# Inputs.net
KiCad netlist of a schematic drawn in Altium Designer
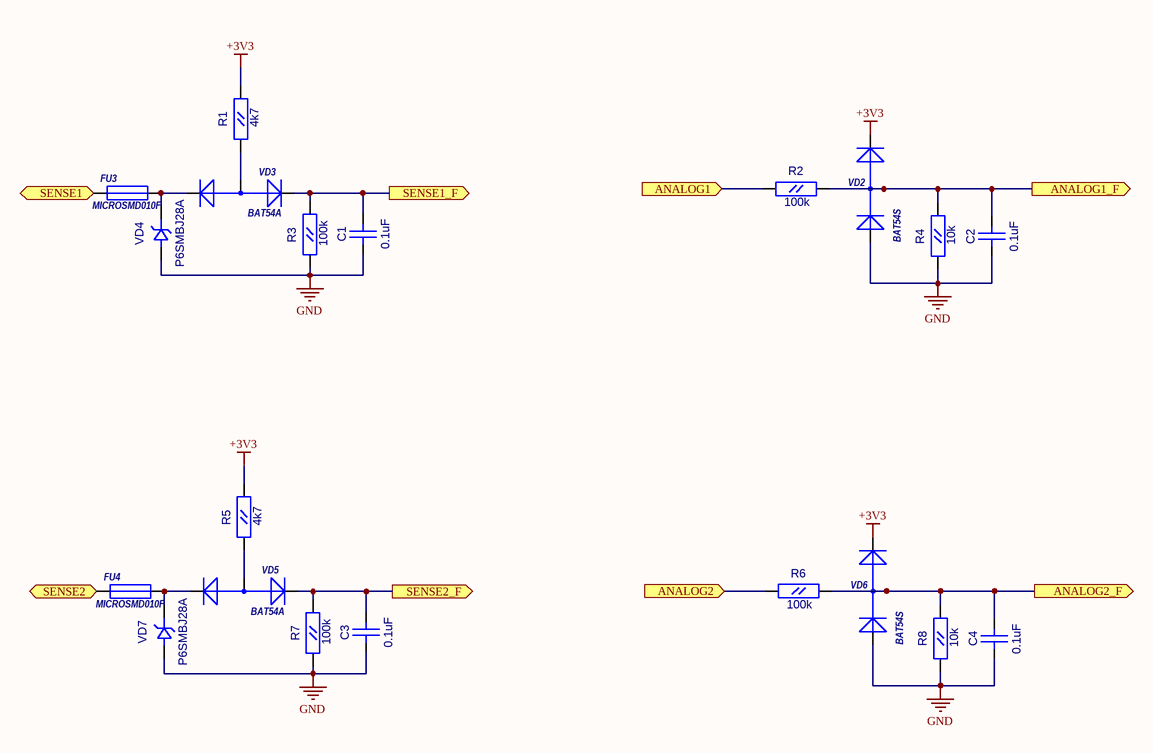
[diagram p0: Inputs.SchDoc]

(export (version "E")
  (design (tool "Eeschema 10.0.6"))
  (components
    (comp (ref "C1")
      (value "0.1uF")
      (footprint "CC0603")
      (description "CC0603")
      (libsource (lib "gprs_modem_2") (part "CC0603"))
    )
    (comp (ref "C2")
      (value "0.1uF")
      (footprint "CC0603")
      (description "CC0603")
      (libsource (lib "gprs_modem_2") (part "CC0603"))
    )
    (comp (ref "C3")
      (value "0.1uF")
      (footprint "CC0603")
      (description "CC0603")
      (libsource (lib "gprs_modem_2") (part "CC0603"))
    )
    (comp (ref "C4")
      (value "0.1uF")
      (footprint "CC0603")
      (description "CC0603")
      (libsource (lib "gprs_modem_2") (part "CC0603"))
    )
    (comp (ref "FU3")
      (value "MICROSMD010F")
      (footprint "RC1210")
      (description "MICROSMD")
      (libsource (lib "gprs_modem_2") (part "MICROSMD"))
    )
    (comp (ref "FU4")
      (value "MICROSMD010F")
      (footprint "RC1210")
      (description "MICROSMD")
      (libsource (lib "gprs_modem_2") (part "MICROSMD"))
    )
    (comp (ref "R1")
      (value "4k7")
      (footprint "RC0603")
      (description "RC0603")
      (libsource (lib "gprs_modem_2") (part "RC0603"))
    )
    (comp (ref "R2")
      (value "100k")
      (footprint "RC0603")
      (description "RC0603")
      (libsource (lib "gprs_modem_2") (part "RC0603"))
    )
    (comp (ref "R3")
      (value "100k")
      (footprint "RC0603")
      (description "RC0603")
      (libsource (lib "gprs_modem_2") (part "RC0603"))
    )
    (comp (ref "R4")
      (value "10k")
      (footprint "RC0603")
      (description "RC0603")
      (libsource (lib "gprs_modem_2") (part "RC0603"))
    )
    (comp (ref "R5")
      (value "4k7")
      (footprint "RC0603")
      (description "RC0603")
      (libsource (lib "gprs_modem_2") (part "RC0603"))
    )
    (comp (ref "R6")
      (value "100k")
      (footprint "RC0603")
      (description "RC0603")
      (libsource (lib "gprs_modem_2") (part "RC0603"))
    )
    (comp (ref "R7")
      (value "100k")
      (footprint "RC0603")
      (description "RC0603")
      (libsource (lib "gprs_modem_2") (part "RC0603"))
    )
    (comp (ref "R8")
      (value "10k")
      (footprint "RC0603")
      (description "RC0603")
      (libsource (lib "gprs_modem_2") (part "RC0603"))
    )
    (comp (ref "VD2")
      (value "BAT54S")
      (footprint "SOT-23(GSD)")
      (description "1.0 Ampere General Purpose Rectifier")
      (libsource (lib "gprs_modem_2") (part "BAT54S"))
    )
    (comp (ref "VD3")
      (value "BAT54A")
      (footprint "SOT-23(123)")
      (description "1.0 Ampere General Purpose Rectifier")
      (libsource (lib "gprs_modem_2") (part "BAT54A"))
    )
    (comp (ref "VD4")
      (value "P6SMBJ28A")
      (footprint "SMB")
      (description "SMBJ")
      (libsource (lib "gprs_modem_2") (part "SMBJ"))
    )
    (comp (ref "VD5")
      (value "BAT54A")
      (footprint "SOT-23(123)")
      (description "1.0 Ampere General Purpose Rectifier")
      (libsource (lib "gprs_modem_2") (part "BAT54A"))
    )
    (comp (ref "VD6")
      (value "BAT54S")
      (footprint "SOT-23(GSD)")
      (description "1.0 Ampere General Purpose Rectifier")
      (libsource (lib "gprs_modem_2") (part "BAT54S"))
    )
    (comp (ref "VD7")
      (value "P6SMBJ28A")
      (footprint "SMB")
      (description "SMBJ")
      (libsource (lib "gprs_modem_2") (part "SMBJ"))
    )
  )
  (nets
    (net (code "1") (name "+3V3") (class "Default")
      (node (ref "R1") (pin "2") (pinfunction "B_2") (pintype "passive"))
      (node (ref "R5") (pin "2") (pinfunction "B_2") (pintype "passive"))
      (node (ref "VD2") (pin "2") (pinfunction "K_2") (pintype "passive"))
      (node (ref "VD6") (pin "2") (pinfunction "K_2") (pintype "passive"))
    )
    (net (code "2") (name "/ANALOG1") (class "Default")
      (node (ref "R2") (pin "1") (pinfunction "A_1") (pintype "passive"))
    )
    (net (code "3") (name "/ANALOG1_F") (class "Default")
      (node (ref "C2") (pin "2") (pinfunction "B_2") (pintype "passive"))
      (node (ref "R2") (pin "2") (pinfunction "B_2") (pintype "passive"))
      (node (ref "R4") (pin "2") (pinfunction "B_2") (pintype "passive"))
      (node (ref "VD2") (pin "3") (pinfunction "AK_3") (pintype "passive"))
    )
    (net (code "4") (name "/ANALOG2") (class "Default")
      (node (ref "R6") (pin "1") (pinfunction "A_1") (pintype "passive"))
    )
    (net (code "5") (name "/ANALOG2_F") (class "Default")
      (node (ref "C4") (pin "2") (pinfunction "B_2") (pintype "passive"))
      (node (ref "R6") (pin "2") (pinfunction "B_2") (pintype "passive"))
      (node (ref "R8") (pin "2") (pinfunction "B_2") (pintype "passive"))
      (node (ref "VD6") (pin "3") (pinfunction "AK_3") (pintype "passive"))
    )
    (net (code "6") (name "/SENSE1") (class "Default") (node (ref "FU3") (pin "1") (pintype "passive")))
    (net (code "7") (name "/SENSE1_F") (class "Default")
      (node (ref "C1") (pin "2") (pinfunction "B_2") (pintype "passive"))
      (node (ref "R3") (pin "2") (pinfunction "B_2") (pintype "passive"))
      (node (ref "VD3") (pin "1") (pinfunction "K_1") (pintype "passive"))
    )
    (net (code "8") (name "/SENSE2") (class "Default") (node (ref "FU4") (pin "1") (pintype "passive")))
    (net (code "9") (name "/SENSE2_F") (class "Default")
      (node (ref "C3") (pin "2") (pinfunction "B_2") (pintype "passive"))
      (node (ref "R7") (pin "2") (pinfunction "B_2") (pintype "passive"))
      (node (ref "VD5") (pin "1") (pinfunction "K_1") (pintype "passive"))
    )
    (net (code "10") (name "GND") (class "Default")
      (node (ref "C1") (pin "1") (pinfunction "A_1") (pintype "passive"))
      (node (ref "C2") (pin "1") (pinfunction "A_1") (pintype "passive"))
      (node (ref "C3") (pin "1") (pinfunction "A_1") (pintype "passive"))
      (node (ref "C4") (pin "1") (pinfunction "A_1") (pintype "passive"))
      (node (ref "R3") (pin "1") (pinfunction "A_1") (pintype "passive"))
      (node (ref "R4") (pin "1") (pinfunction "A_1") (pintype "passive"))
      (node (ref "R7") (pin "1") (pinfunction "A_1") (pintype "passive"))
      (node (ref "R8") (pin "1") (pinfunction "A_1") (pintype "passive"))
      (node (ref "VD2") (pin "1") (pinfunction "A_1") (pintype "passive"))
      (node (ref "VD4") (pin "1") (pinfunction "A_1") (pintype "passive"))
      (node (ref "VD6") (pin "1") (pinfunction "A_1") (pintype "passive"))
      (node (ref "VD7") (pin "1") (pinfunction "A_1") (pintype "passive"))
    )
    (net (code "11") (name "Net-(R1-A)") (class "Default")
      (node (ref "R1") (pin "1") (pinfunction "A_1") (pintype "passive"))
      (node (ref "VD3") (pin "3") (pinfunction "A_3") (pintype "passive"))
    )
    (net (code "12") (name "Net-(R5-A)") (class "Default")
      (node (ref "R5") (pin "1") (pinfunction "A_1") (pintype "passive"))
      (node (ref "VD5") (pin "3") (pinfunction "A_3") (pintype "passive"))
    )
    (net (code "13") (name "Net-(VD4-K)") (class "Default")
      (node (ref "FU3") (pin "2") (pintype "passive"))
      (node (ref "VD3") (pin "2") (pinfunction "K_2") (pintype "passive"))
      (node (ref "VD4") (pin "2") (pinfunction "K_2") (pintype "passive"))
    )
    (net (code "14") (name "Net-(VD7-K)") (class "Default")
      (node (ref "FU4") (pin "2") (pintype "passive"))
      (node (ref "VD5") (pin "2") (pinfunction "K_2") (pintype "passive"))
      (node (ref "VD7") (pin "2") (pinfunction "K_2") (pintype "passive"))
    )
  )
)
